# 13_iMX_8X_SYSTEM.net
KiCad netlist of a schematic drawn in Altium Designer
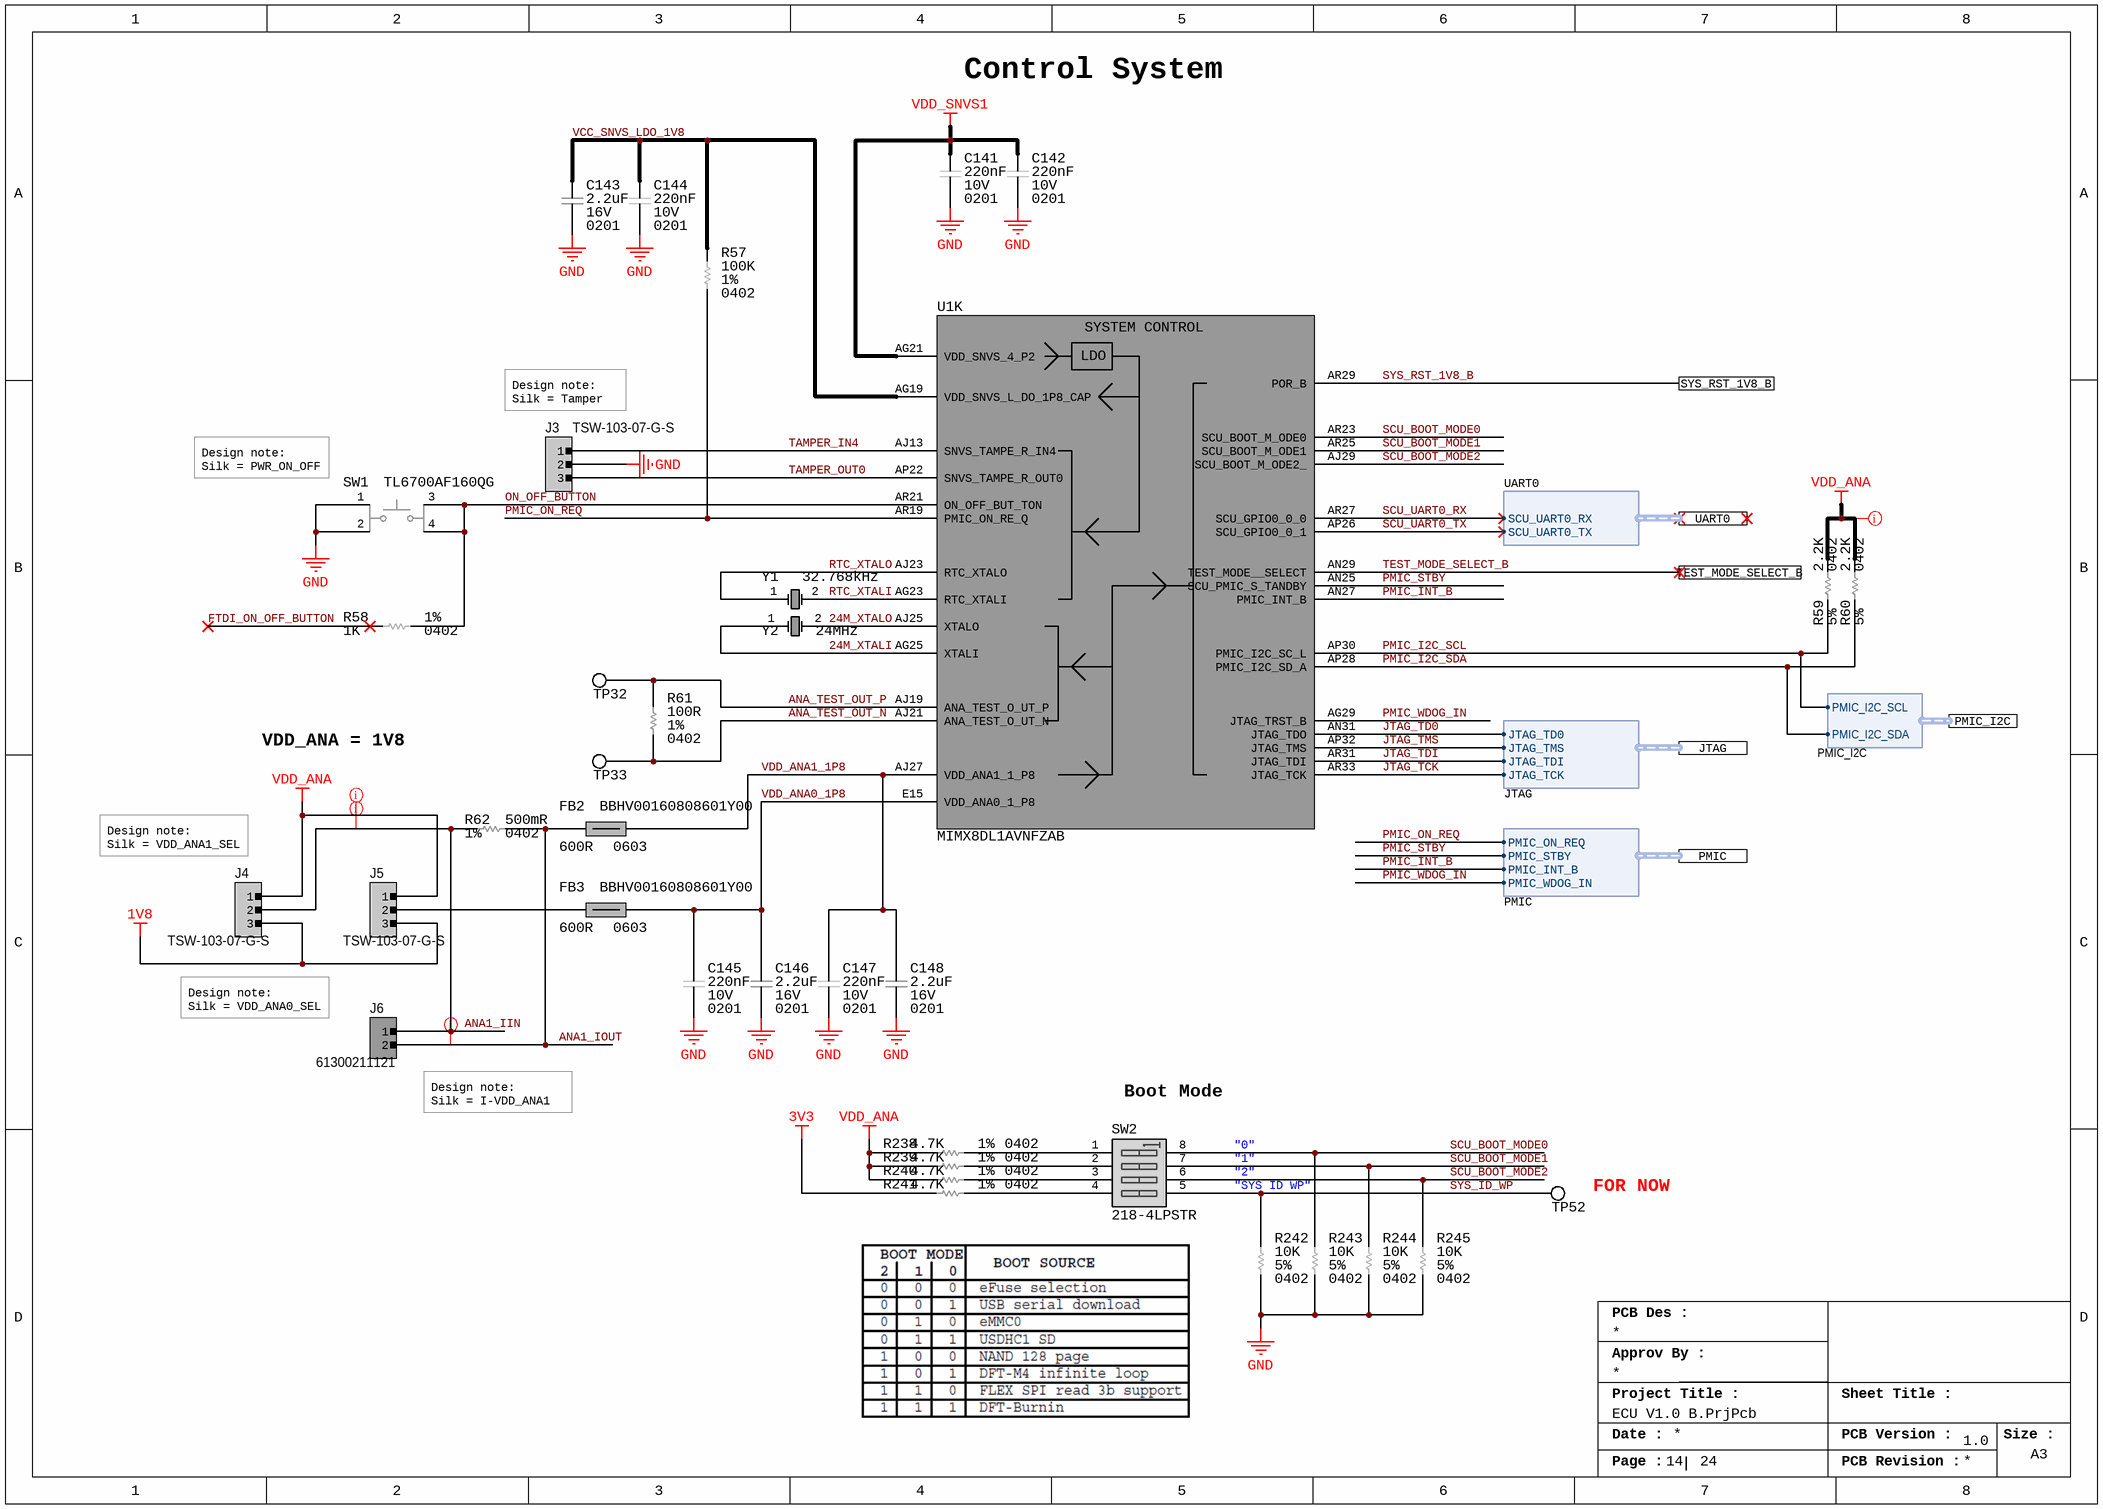
[diagram p0: 13_iMX 8X_SYSTEM.SchDoc]

(export (version "E")
  (design (tool "Eeschema 10.0.6"))
  (components
    (comp (ref "C141")
      (value "LMK063BJ224MP-F")
      (footprint "CAP_0201_CAPC0603X03N")
      (description "Multilayer Ceramic Capacitors (High dielectric type), 10V, 0.22 uF, ± 20 %, 0201, X5R, RoHS")
      (fields
        (field (name "MANUFACTURER") "Taiyo Yuden")
        (field (name "TOLERANCE") "20%")
        (field (name "VOLTAGE RATING (DC)") "10V")
        (field (name "CAPACITANCE") "220nF")
        (field (name "CASE/PACKAGE") "0201")
      )
      (libsource (lib "Electronic Devices_LIB") (part "CAP_0.22UF_10V_X5R_0201"))
    )
    (comp (ref "C142")
      (value "LMK063BJ224MP-F")
      (footprint "CAP_0201_CAPC0603X03N")
      (description "Multilayer Ceramic Capacitors (High dielectric type), 10V, 0.22 uF, ± 20 %, 0201, X5R, RoHS")
      (fields
        (field (name "MANUFACTURER") "Taiyo Yuden")
        (field (name "TOLERANCE") "20%")
        (field (name "VOLTAGE RATING (DC)") "10V")
        (field (name "CAPACITANCE") "220nF")
        (field (name "CASE/PACKAGE") "0201")
      )
      (libsource (lib "Electronic Devices_LIB") (part "CAP_0.22UF_10V_X5R_0201"))
    )
    (comp (ref "C143")
      (value "GRM035R61C225ME01D")
      (footprint "CAP_0201_CAPC0603X03N")
      (description "General Up to 85C Reflow soldering")
      (fields
        (field (name "MANUFACTURER") "Murata")
        (field (name "TOLERANCE") "20%")
        (field (name "CAPACITANCE") "2.2uF")
        (field (name "VOLTAGE RATING") "16V")
        (field (name "CASE/PACKAGE") "0201")
      )
      (libsource (lib "Electronic Devices_LIB") (part "CAP_2.2uF_16V_X5R_0201"))
    )
    (comp (ref "C144")
      (value "LMK063BJ224MP-F")
      (footprint "CAP_0201_CAPC0603X03N")
      (description "Multilayer Ceramic Capacitors (High dielectric type), 10V, 0.22 uF, ± 20 %, 0201, X5R, RoHS")
      (fields
        (field (name "MANUFACTURER") "Taiyo Yuden")
        (field (name "TOLERANCE") "20%")
        (field (name "VOLTAGE RATING (DC)") "10V")
        (field (name "CAPACITANCE") "220nF")
        (field (name "CASE/PACKAGE") "0201")
      )
      (libsource (lib "Electronic Devices_LIB") (part "CAP_0.22UF_10V_X5R_0201"))
    )
    (comp (ref "C145")
      (value "LMK063BJ224MP-F")
      (footprint "CAP_0201_CAPC0603X03N")
      (description "Multilayer Ceramic Capacitors (High dielectric type), 10V, 0.22 uF, ± 20 %, 0201, X5R, RoHS")
      (fields
        (field (name "MANUFACTURER") "Taiyo Yuden")
        (field (name "TOLERANCE") "20%")
        (field (name "VOLTAGE RATING (DC)") "10V")
        (field (name "CAPACITANCE") "220nF")
        (field (name "CASE/PACKAGE") "0201")
      )
      (libsource (lib "Electronic Devices_LIB") (part "CAP_0.22UF_10V_X5R_0201"))
    )
    (comp (ref "C146")
      (value "GRM035R61C225ME01D")
      (footprint "CAP_0201_CAPC0603X03N")
      (description "General Up to 85C Reflow soldering")
      (fields
        (field (name "MANUFACTURER") "Murata")
        (field (name "TOLERANCE") "20%")
        (field (name "CAPACITANCE") "2.2uF")
        (field (name "VOLTAGE RATING") "16V")
        (field (name "CASE/PACKAGE") "0201")
      )
      (libsource (lib "Electronic Devices_LIB") (part "CAP_2.2uF_16V_X5R_0201"))
    )
    (comp (ref "C147")
      (value "LMK063BJ224MP-F")
      (footprint "CAP_0201_CAPC0603X03N")
      (description "Multilayer Ceramic Capacitors (High dielectric type), 10V, 0.22 uF, ± 20 %, 0201, X5R, RoHS")
      (fields
        (field (name "MANUFACTURER") "Taiyo Yuden")
        (field (name "TOLERANCE") "20%")
        (field (name "VOLTAGE RATING (DC)") "10V")
        (field (name "CAPACITANCE") "220nF")
        (field (name "CASE/PACKAGE") "0201")
      )
      (libsource (lib "Electronic Devices_LIB") (part "CAP_0.22UF_10V_X5R_0201"))
    )
    (comp (ref "C148")
      (value "GRM035R61C225ME01D")
      (footprint "CAP_0201_CAPC0603X03N")
      (description "General Up to 85C Reflow soldering")
      (fields
        (field (name "MANUFACTURER") "Murata")
        (field (name "TOLERANCE") "20%")
        (field (name "CAPACITANCE") "2.2uF")
        (field (name "VOLTAGE RATING") "16V")
        (field (name "CASE/PACKAGE") "0201")
      )
      (libsource (lib "Electronic Devices_LIB") (part "CAP_2.2uF_16V_X5R_0201"))
    )
    (comp (ref "FB2")
      (value "BBHV00160808601Y00")
      (footprint "IND_0603_INDC1608X08N")
      (description "Ferrite Chip Bead 600Ohm 2A 0.1Ohm Multilayer 2-Pin 0603 T/R")
      (fields
        (field (name "MANUFACTURER") "Pulse")
        (field (name "IMPEDANCE") "600R")
        (field (name "CASE") "0603")
      )
      (libsource (lib "Electronic Devices_LIB") (part "IND_FERRITE_BEADS_600R_2A_BBHV00160808601Y00"))
    )
    (comp (ref "FB3")
      (value "BBHV00160808601Y00")
      (footprint "IND_0603_INDC1608X08N")
      (description "Ferrite Chip Bead 600Ohm 2A 0.1Ohm Multilayer 2-Pin 0603 T/R")
      (fields
        (field (name "MANUFACTURER") "Pulse")
        (field (name "IMPEDANCE") "600R")
        (field (name "CASE") "0603")
      )
      (libsource (lib "Electronic Devices_LIB") (part "IND_FERRITE_BEADS_600R_2A_BBHV00160808601Y00"))
    )
    (comp (ref "J3")
      (value "TSW-103-07-G-S")
      (footprint "CONN_HEADER_MALE_SAMTEC_TSW-103-07-G-S")
      (description "Conn Unshrouded Header HDR 3 POS 2.54mm Solder ST Top Entry Thru-Hole Bulk")
      (fields (field (name "MANUFACTURER") "Samtec"))
      (libsource (lib "Electronic Devices_LIB") (part "CONN_HEADER_MALE_3P_2.54mm_TSW-103-07-G-S"))
    )
    (comp (ref "J4")
      (value "TSW-103-07-G-S")
      (footprint "CONN_HEADER_MALE_SAMTEC_TSW-103-07-G-S")
      (description "Conn Unshrouded Header HDR 3 POS 2.54mm Solder ST Top Entry Thru-Hole Bulk")
      (fields (field (name "MANUFACTURER") "Samtec"))
      (libsource (lib "Electronic Devices_LIB") (part "CONN_HEADER_MALE_3P_2.54mm_TSW-103-07-G-S"))
    )
    (comp (ref "J5")
      (value "TSW-103-07-G-S")
      (footprint "CONN_HEADER_MALE_SAMTEC_TSW-103-07-G-S")
      (description "Conn Unshrouded Header HDR 3 POS 2.54mm Solder ST Top Entry Thru-Hole Bulk")
      (fields (field (name "MANUFACTURER") "Samtec"))
      (libsource (lib "Electronic Devices_LIB") (part "CONN_HEADER_MALE_3P_2.54mm_TSW-103-07-G-S"))
    )
    (comp (ref "J6")
      (value "61300211121")
      (footprint "HEADER_MALE_HDRV2W110P0X254_1X2_508X254X854P")
      (description "THT Vertical Pin Header WR-PHD, Pitch 2.54 mm, Single Row, 2 pins")
      (fields (field (name "MANUFACTURER") "Wurth Electronics"))
      (libsource (lib "Electronic Devices_LIB") (part "CONN_HEADER_MALE_2P_2.54_61300211121"))
    )
    (comp (ref "R57")
      (value "RC0402FR-07100KL")
      (footprint "RES_0402_RESC1005X04N")
      (description "SMD Chip Resistor, 100 kOhm, ± 1%, 63 mW, 0402 [1005 Metric], Thick Film, General Purpose")
      (fields
        (field (name "MANUFACTURER") "Yageo")
        (field (name "RESISTANCE") "100K")
        (field (name "TOLERANCE") "1%")
        (field (name "CASE/PACKAGE") "0402")
      )
      (libsource (lib "Electronic Devices_LIB") (part "RES_100K_1%_100mW_0402"))
    )
    (comp (ref "R58")
      (value "ERJ-2RKF1001X")
      (footprint "RES_0402_RESC1005X04N")
      (description "RES SMD 1K OHM 1% 1/10W 0402")
      (fields
        (field (name "MANUFACTURER") "Panasonic")
        (field (name "RESISTANCE") "1K")
        (field (name "TOLERANCE") "1%")
        (field (name "CASE/PACKAGE") "0402")
      )
      (libsource (lib "Electronic Devices_LIB") (part "RES_1K_1%_100mW_0402"))
    )
    (comp (ref "R59")
      (value "RC0402JR-072K2L")
      (footprint "RES_0402_RESC1005X04N")
      (description "SMD Chip Resistor, 2.2 kOhm, ± 5%, 63 mW, 0402 [1005 Metric], Thick Film, General Purpose")
      (fields
        (field (name "MANUFACTURER") "Yageo")
        (field (name "TOLERANCE") "5%")
        (field (name "RESISTANCE") "2.2K")
        (field (name "CASE/PACKAGE") "0402")
      )
      (libsource (lib "Electronic Devices_LIB") (part "RES_2.2K_5%_63mW_0402"))
    )
    (comp (ref "R60")
      (value "RC0402JR-072K2L")
      (footprint "RES_0402_RESC1005X04N")
      (description "SMD Chip Resistor, 2.2 kOhm, ± 5%, 63 mW, 0402 [1005 Metric], Thick Film, General Purpose")
      (fields
        (field (name "MANUFACTURER") "Yageo")
        (field (name "TOLERANCE") "5%")
        (field (name "RESISTANCE") "2.2K")
        (field (name "CASE/PACKAGE") "0402")
      )
      (libsource (lib "Electronic Devices_LIB") (part "RES_2.2K_5%_63mW_0402"))
    )
    (comp (ref "R61")
      (value "ERJ-2RKF1000X")
      (footprint "RES_0402_RESC1005X04N")
      (description "Resistor Thick Film 0402 100 Ohm 1% 1/10W 100ppm/C Molded SMD Punched Carrier T/R")
      (fields
        (field (name "MANUFACTURER") "Panasonic")
        (field (name "TOLERANCE") "1%")
        (field (name "RESISTANCE") "100R")
        (field (name "CASE/PACKAGE") "0402")
      )
      (libsource (lib "Electronic Devices_LIB") (part "RES_100R_1%_100mW_0402"))
    )
    (comp (ref "R62")
      (value "RL0402FR-070R5L")
      (footprint "RES_0603_RESC1608X04N")
      (description "SMD Current Sense Resistor, 0.5 ohm, RL Series, 0402 [1005 Metric], 63 mW, ï¿½ 1%, Thick Film")
      (fields
        (field (name "MANUFACTURER") "Yageo")
        (field (name "CASE/PACKAGE") "0402")
        (field (name "TOLERANCE") "1%")
        (field (name "RESISTANCE") "500mR")
      )
      (libsource (lib "Electronic Devices_LIB") (part "RES_0.5R_63mW_0402"))
    )
    (comp (ref "R238")
      (value "ERJ-2RKF4701X")
      (footprint "RES_0402_RESC1005X04N")
      (description "Res Thick Film 0402 4.7K Ohm 1% 0.1W ±100ppm/°C Molded SMD Punched Carrier T/R")
      (fields
        (field (name "MANUFACTURER") "Panasonic")
        (field (name "TOLERANCE") "1%")
        (field (name "CASE CODE (IMPERIAL)") "0402")
        (field (name "RESISTANCE") "4.7K")
      )
      (libsource (lib "Electronic Devices_LIB") (part "RES_4.7K_1%_100mW_0402"))
    )
    (comp (ref "R239")
      (value "ERJ-2RKF4701X")
      (footprint "RES_0402_RESC1005X04N")
      (description "Res Thick Film 0402 4.7K Ohm 1% 0.1W ±100ppm/°C Molded SMD Punched Carrier T/R")
      (fields
        (field (name "MANUFACTURER") "Panasonic")
        (field (name "TOLERANCE") "1%")
        (field (name "CASE CODE (IMPERIAL)") "0402")
        (field (name "RESISTANCE") "4.7K")
      )
      (libsource (lib "Electronic Devices_LIB") (part "RES_4.7K_1%_100mW_0402"))
    )
    (comp (ref "R240")
      (value "ERJ-2RKF4701X")
      (footprint "RES_0402_RESC1005X04N")
      (description "Res Thick Film 0402 4.7K Ohm 1% 0.1W ±100ppm/°C Molded SMD Punched Carrier T/R")
      (fields
        (field (name "MANUFACTURER") "Panasonic")
        (field (name "TOLERANCE") "1%")
        (field (name "CASE CODE (IMPERIAL)") "0402")
        (field (name "RESISTANCE") "4.7K")
      )
      (libsource (lib "Electronic Devices_LIB") (part "RES_4.7K_1%_100mW_0402"))
    )
    (comp (ref "R241")
      (value "ERJ-2RKF4701X")
      (footprint "RES_0402_RESC1005X04N")
      (description "Res Thick Film 0402 4.7K Ohm 1% 0.1W ±100ppm/°C Molded SMD Punched Carrier T/R")
      (fields
        (field (name "MANUFACTURER") "Panasonic")
        (field (name "TOLERANCE") "1%")
        (field (name "CASE CODE (IMPERIAL)") "0402")
        (field (name "RESISTANCE") "4.7K")
      )
      (libsource (lib "Electronic Devices_LIB") (part "RES_4.7K_1%_100mW_0402"))
    )
    (comp (ref "R242")
      (value "ERJ-2GEJ103X")
      (footprint "RES_0402_RESC1005X04N")
      (description "Res Thick Film 0402 10K Ohm 5% 1/10W ±200ppm/°C Molded SMD Punched Carrier T/R")
      (fields
        (field (name "MANUFACTURER") "Panasonic")
        (field (name "TOLERANCE") "5%")
        (field (name "RESISTANCE") "10K")
        (field (name "CASE/PACKAGE") "0402")
      )
      (libsource (lib "Electronic Devices_LIB") (part "RES_10K_5%_100mW_0402"))
    )
    (comp (ref "R243")
      (value "ERJ-2GEJ103X")
      (footprint "RES_0402_RESC1005X04N")
      (description "Res Thick Film 0402 10K Ohm 5% 1/10W ±200ppm/°C Molded SMD Punched Carrier T/R")
      (fields
        (field (name "MANUFACTURER") "Panasonic")
        (field (name "TOLERANCE") "5%")
        (field (name "RESISTANCE") "10K")
        (field (name "CASE/PACKAGE") "0402")
      )
      (libsource (lib "Electronic Devices_LIB") (part "RES_10K_5%_100mW_0402"))
    )
    (comp (ref "R244")
      (value "ERJ-2GEJ103X")
      (footprint "RES_0402_RESC1005X04N")
      (description "Res Thick Film 0402 10K Ohm 5% 1/10W ±200ppm/°C Molded SMD Punched Carrier T/R")
      (fields
        (field (name "MANUFACTURER") "Panasonic")
        (field (name "TOLERANCE") "5%")
        (field (name "RESISTANCE") "10K")
        (field (name "CASE/PACKAGE") "0402")
      )
      (libsource (lib "Electronic Devices_LIB") (part "RES_10K_5%_100mW_0402"))
    )
    (comp (ref "R245")
      (value "ERJ-2GEJ103X")
      (footprint "RES_0402_RESC1005X04N")
      (description "Res Thick Film 0402 10K Ohm 5% 1/10W ±200ppm/°C Molded SMD Punched Carrier T/R")
      (fields
        (field (name "MANUFACTURER") "Panasonic")
        (field (name "TOLERANCE") "5%")
        (field (name "RESISTANCE") "10K")
        (field (name "CASE/PACKAGE") "0402")
      )
      (libsource (lib "Electronic Devices_LIB") (part "RES_10K_5%_100mW_0402"))
    )
    (comp (ref "SW1")
      (value "TL6700AF160QG")
      (footprint "SW_TL6700AF160QG")
      (description "TL6700 Series SPST 1.6 N Round Button Gull Wing SMT Sealed Tactile Switch")
      (fields (field (name "MANUFACTURER") "E-Switch"))
      (libsource (lib "Electronic Devices_LIB") (part "SWITCH_SPST_TL6700AF160QG"))
    )
    (comp (ref "SW2")
      (value "218-4LPSTR")
      (footprint "SW_DIP_SOIC127P844X265-8N")
      (description "Switch DIP ON OFF SPST 4 Recessed Slide 0.025A 24VDC Gull Wing 1000Cycles 1.27mm SMD T/R")
      (fields (field (name "MANUFACTURER") "CTS"))
      (libsource (lib "Electronic Devices_LIB") (part "SWITCH_DIP_4P_25mA_218-4LPSTR"))
    )
    (comp (ref "TP32")
      (value "NO COMPONENT")
      (footprint "TP_PAD_0.5MM_SMD_ROUND")
      (description "Test Point, SMD pad, round, 1.5mm, 1.6mm, 3mm diameter")
      (libsource (lib "Electronic Devices_LIB") (part "TP_PAD_SMD_SMALL"))
    )
    (comp (ref "TP33")
      (value "NO COMPONENT")
      (footprint "TP_PAD_0.5MM_SMD_ROUND")
      (description "Test Point, SMD pad, round, 1.5mm, 1.6mm, 3mm diameter")
      (libsource (lib "Electronic Devices_LIB") (part "TP_PAD_SMD_SMALL"))
    )
    (comp (ref "TP52")
      (value "NO COMPONENT")
      (footprint "TP_PAD_0.5MM_SMD_ROUND")
      (description "Test Point, SMD pad, round, 1.5mm, 1.6mm, 3mm diameter")
      (libsource (lib "Electronic Devices_LIB") (part "TP_PAD_SMD_SMALL"))
    )
    (comp (ref "U1")
      (value "MIMX8DL1AVNFZAB")
      (footprint "MIMX8DL1AVNFZAB")
      (description "I.MX8 Dxl 15SQ / Tray Rohs Compliant: Yes")
      (fields (field (name "MANUFACTURER") "NXP Semiconductors"))
      (libsource (lib "Electronic Devices_LIB") (part "IC_MPU_ARM_1.2GHz_MIMX8DL1AVNFZAB"))
    )
    (comp (ref "Y1")
      (value "FC-135 32.7680KA-AG5")
      (footprint "CRYSTAL_FC135327680KAAG5")
      (description "Crystal 0.032768MHz ±20ppm (Tol) 7pF FUND 70000Ohm 2-Pin SMD T/R")
      (fields (field (name "MANUFACTURER") "Epson") (field (name "FREQUENCY") "32.768kHz"))
      (libsource (lib "Electronic Devices_LIB") (part "CRYSTAL_EPSON_32.768KHZ"))
    )
    (comp (ref "Y2")
      (value "ECS-240-18-23A-EN-TR")
      (footprint "CRYSTAL_ECS-240-18-23A-EN-TR")
      (description "Crystal 24MHz ±30ppm (Tol) ±50ppm (Stability) 18pF FUND 30Ohm 2-Pin Mini-SMD T/R")
      (fields (field (name "MANUFACTURER") "ECS International") (field (name "FREQUENCY") "24MHz"))
      (libsource (lib "Electronic Devices_LIB") (part "CRYSTAL_ECS_24MHZ"))
    )
  )
  (nets
    (net (code "5") (name "/24M_XTALI") (class "Default")
      (node (ref "U1") (pin "AG25") (pinfunction "XTALI_AG25") (pintype "passive"))
      (node (ref "Y2") (pin "1") (pinfunction "OSC1_1") (pintype "passive"))
    )
    (net (code "6") (name "/24M_XTALO") (class "Default")
      (node (ref "U1") (pin "AJ25") (pinfunction "XTALO_AJ25") (pintype "passive"))
      (node (ref "Y2") (pin "2") (pinfunction "OSC2_2") (pintype "passive"))
    )
    (net (code "7") (name "/ANA1_IIN") (class "Default")
      (node (ref "J4") (pin "2") (pinfunction "2_2") (pintype "passive"))
      (node (ref "J6") (pin "1") (pinfunction "1_1") (pintype "passive"))
      (node (ref "R62") (pin "1") (pinfunction "1_1") (pintype "passive"))
    )
    (net (code "8") (name "/ANA1_IOUT") (class "Default")
      (node (ref "FB2") (pin "1") (pinfunction "1_1") (pintype "passive"))
      (node (ref "J6") (pin "2") (pinfunction "2_2") (pintype "passive"))
      (node (ref "R62") (pin "2") (pinfunction "2_2") (pintype "passive"))
    )
    (net (code "9") (name "/ANA_TEST_OUT_N") (class "Default")
      (node (ref "R61") (pin "1") (pinfunction "1_1") (pintype "passive"))
      (node (ref "TP33") (pin "1") (pinfunction "1_1") (pintype "passive"))
      (node (ref "U1") (pin "AJ21") (pinfunction "ANA_TEST_O_UT_N_AJ21") (pintype "passive"))
    )
    (net (code "10") (name "/ANA_TEST_OUT_P") (class "Default")
      (node (ref "R61") (pin "2") (pinfunction "2_2") (pintype "passive"))
      (node (ref "TP32") (pin "1") (pinfunction "1_1") (pintype "passive"))
      (node (ref "U1") (pin "AJ19") (pinfunction "ANA_TEST_O_UT_P_AJ19") (pintype "passive"))
    )
    (net (code "11") (name "/FTDI_ON_OFF_BUTTON") (class "Default")
      (node (ref "R58") (pin "1") (pinfunction "1_1") (pintype "passive+no_connect"))
    )
    (net (code "12") (name "/JTAG_TCK") (class "Default")
      (node (ref "U1") (pin "AR33") (pinfunction "JTAG_TCK_AR33") (pintype "passive"))
    )
    (net (code "13") (name "/JTAG_TD0") (class "Default")
      (node (ref "U1") (pin "AN31") (pinfunction "JTAG_TDO_AN31") (pintype "passive"))
    )
    (net (code "14") (name "/JTAG_TDI") (class "Default")
      (node (ref "U1") (pin "AR31") (pinfunction "JTAG_TDI_AR31") (pintype "passive"))
    )
    (net (code "15") (name "/JTAG_TMS") (class "Default")
      (node (ref "U1") (pin "AP32") (pinfunction "JTAG_TMS_AP32") (pintype "passive"))
    )
    (net (code "16") (name "/ON_OFF_BUTTON") (class "Default")
      (node (ref "R58") (pin "2") (pinfunction "2_2") (pintype "passive"))
      (node (ref "SW1") (pin "3") (pinfunction "3_3") (pintype "passive"))
      (node (ref "SW1") (pin "4") (pinfunction "4_4") (pintype "passive"))
      (node (ref "U1") (pin "AR21") (pinfunction "ON_OFF_BUT_TON_AR21") (pintype "passive"))
    )
    (net (code "17") (name "/PMIC_I2C_SCL") (class "Default")
      (node (ref "R59") (pin "1") (pinfunction "1_1") (pintype "passive"))
      (node (ref "U1") (pin "AP30") (pinfunction "PMIC_I2C_SC_L_AP30") (pintype "passive"))
    )
    (net (code "18") (name "/PMIC_I2C_SDA") (class "Default")
      (node (ref "R60") (pin "1") (pinfunction "1_1") (pintype "passive"))
      (node (ref "U1") (pin "AP28") (pinfunction "PMIC_I2C_SD_A_AP28") (pintype "passive"))
    )
    (net (code "19") (name "/PMIC_INT_B") (class "Default")
      (node (ref "U1") (pin "AN27") (pinfunction "PMIC_INT_B_AN27") (pintype "passive"))
    )
    (net (code "20") (name "/PMIC_ON_REQ") (class "Default")
      (node (ref "R57") (pin "1") (pinfunction "1_1") (pintype "passive"))
      (node (ref "U1") (pin "AR19") (pinfunction "PMIC_ON_RE_Q_AR19") (pintype "passive"))
    )
    (net (code "21") (name "/PMIC_STBY") (class "Default")
      (node (ref "U1") (pin "AN25") (pinfunction "SCU_PMIC_S_TANDBY_AN25") (pintype "passive"))
    )
    (net (code "22") (name "/PMIC_WDOG_IN") (class "Default")
      (node (ref "U1") (pin "AG29") (pinfunction "JTAG_TRST_B_AG29") (pintype "passive"))
    )
    (net (code "23") (name "/RTC_XTALI") (class "Default")
      (node (ref "U1") (pin "AG23") (pinfunction "RTC_XTALI_AG23") (pintype "passive"))
      (node (ref "Y1") (pin "2") (pinfunction "OSC2_2") (pintype "passive"))
    )
    (net (code "24") (name "/RTC_XTALO") (class "Default")
      (node (ref "U1") (pin "AJ23") (pinfunction "RTC_XTALO_AJ23") (pintype "passive"))
      (node (ref "Y1") (pin "1") (pinfunction "OSC1_1") (pintype "passive"))
    )
    (net (code "25") (name "/SCU_BOOT_MODE0") (class "Default")
      (node (ref "R243") (pin "1") (pinfunction "1_1") (pintype "passive"))
      (node (ref "SW2") (pin "8") (pinfunction "B1_8") (pintype "passive"))
      (node (ref "U1") (pin "AR23") (pinfunction "SCU_BOOT_M_ODE0_AR23") (pintype "passive"))
    )
    (net (code "26") (name "/SCU_BOOT_MODE1") (class "Default")
      (node (ref "R244") (pin "1") (pinfunction "1_1") (pintype "passive"))
      (node (ref "SW2") (pin "7") (pinfunction "B2_7") (pintype "passive"))
      (node (ref "U1") (pin "AR25") (pinfunction "SCU_BOOT_M_ODE1_AR25") (pintype "passive"))
    )
    (net (code "27") (name "/SCU_BOOT_MODE2") (class "Default")
      (node (ref "R245") (pin "1") (pinfunction "1_1") (pintype "passive"))
      (node (ref "SW2") (pin "6") (pinfunction "B3_6") (pintype "passive"))
      (node (ref "U1") (pin "AJ29") (pinfunction "SCU_BOOT_M_ODE2__AJ29") (pintype "passive"))
    )
    (net (code "28") (name "/SCU_UART0_RX") (class "Default")
      (node (ref "U1") (pin "AR27") (pinfunction "SCU_GPIO0_0_0_AR27") (pintype "passive+no_connect"))
    )
    (net (code "29") (name "/SCU_UART0_TX") (class "Default")
      (node (ref "U1") (pin "AP26") (pinfunction "SCU_GPIO0_0_1_AP26") (pintype "passive+no_connect"))
    )
    (net (code "30") (name "/SYS_ID_WP") (class "Default")
      (node (ref "R242") (pin "1") (pinfunction "1_1") (pintype "passive"))
      (node (ref "SW2") (pin "5") (pinfunction "B4_5") (pintype "passive"))
      (node (ref "TP52") (pin "1") (pinfunction "1_1") (pintype "passive"))
    )
    (net (code "31") (name "/SYS_RST_1V8_B") (class "Default")
      (node (ref "U1") (pin "AR29") (pinfunction "POR_B_AR29") (pintype "passive"))
    )
    (net (code "32") (name "/TAMPER_IN4") (class "Default")
      (node (ref "J3") (pin "1") (pinfunction "1_1") (pintype "passive"))
      (node (ref "U1") (pin "AJ13") (pinfunction "SNVS_TAMPE_R_IN4_AJ13") (pintype "passive"))
    )
    (net (code "33") (name "/TAMPER_OUT0") (class "Default")
      (node (ref "J3") (pin "3") (pinfunction "3_3") (pintype "passive"))
      (node (ref "U1") (pin "AP22") (pinfunction "SNVS_TAMPE_R_OUT0_AP22") (pintype "passive"))
    )
    (net (code "34") (name "/TEST_MODE_SELECT_B") (class "Default")
      (node (ref "U1") (pin "AN29") (pinfunction "TEST_MODE__SELECT_AN29") (pintype "passive+no_connect"))
    )
    (net (code "35") (name "/VCC_SNVS_LDO_1V8") (class "Default")
      (node (ref "C143") (pin "2") (pinfunction "2_2") (pintype "passive"))
      (node (ref "C144") (pin "2") (pinfunction "2_2") (pintype "passive"))
      (node (ref "R57") (pin "2") (pinfunction "2_2") (pintype "passive"))
      (node (ref "U1") (pin "AG19") (pinfunction "VDD_SNVS_L_DO_1P8_CAP_AG19") (pintype "passive"))
    )
    (net (code "36") (name "/VDD_ANA0_1P8") (class "Default")
      (node (ref "C145") (pin "2") (pinfunction "2_2") (pintype "passive"))
      (node (ref "C146") (pin "2") (pinfunction "2_2") (pintype "passive"))
      (node (ref "FB3") (pin "2") (pinfunction "2_2") (pintype "passive"))
      (node (ref "U1") (pin "E15") (pinfunction "VDD_ANA0_1_P8_E15") (pintype "passive"))
    )
    (net (code "37") (name "/VDD_ANA1_1P8") (class "Default")
      (node (ref "C147") (pin "2") (pinfunction "2_2") (pintype "passive"))
      (node (ref "C148") (pin "2") (pinfunction "2_2") (pintype "passive"))
      (node (ref "FB2") (pin "2") (pinfunction "2_2") (pintype "passive"))
      (node (ref "U1") (pin "AJ27") (pinfunction "VDD_ANA1_1_P8_AJ27") (pintype "passive"))
    )
    (net (code "42") (name "1V8") (class "Default")
      (node (ref "J4") (pin "3") (pinfunction "3_3") (pintype "passive"))
      (node (ref "J5") (pin "3") (pinfunction "3_3") (pintype "passive"))
    )
    (net (code "43") (name "3V3") (class "Default")
      (node (ref "R241") (pin "1") (pinfunction "1_1") (pintype "passive"))
    )
    (net (code "44") (name "GND") (class "Default")
      (node (ref "C141") (pin "1") (pinfunction "1_1") (pintype "passive"))
      (node (ref "C142") (pin "1") (pinfunction "1_1") (pintype "passive"))
      (node (ref "C143") (pin "1") (pinfunction "1_1") (pintype "passive"))
      (node (ref "C144") (pin "1") (pinfunction "1_1") (pintype "passive"))
      (node (ref "C145") (pin "1") (pinfunction "1_1") (pintype "passive"))
      (node (ref "C146") (pin "1") (pinfunction "1_1") (pintype "passive"))
      (node (ref "C147") (pin "1") (pinfunction "1_1") (pintype "passive"))
      (node (ref "C148") (pin "1") (pinfunction "1_1") (pintype "passive"))
      (node (ref "J3") (pin "2") (pinfunction "2_2") (pintype "passive"))
      (node (ref "R242") (pin "2") (pinfunction "2_2") (pintype "passive"))
      (node (ref "R243") (pin "2") (pinfunction "2_2") (pintype "passive"))
      (node (ref "R244") (pin "2") (pinfunction "2_2") (pintype "passive"))
      (node (ref "R245") (pin "2") (pinfunction "2_2") (pintype "passive"))
      (node (ref "SW1") (pin "1") (pinfunction "1_1") (pintype "passive"))
      (node (ref "SW1") (pin "2") (pinfunction "2_2") (pintype "passive"))
    )
    (net (code "45") (name "Net-(FB3-Pad1)") (class "Default")
      (node (ref "FB3") (pin "1") (pinfunction "1_1") (pintype "passive"))
      (node (ref "J5") (pin "2") (pinfunction "2_2") (pintype "passive"))
    )
    (net (code "46") (name "Net-(SW2-A1)") (class "Default")
      (node (ref "R238") (pin "2") (pinfunction "2_2") (pintype "passive"))
      (node (ref "SW2") (pin "1") (pinfunction "A1_1") (pintype "passive"))
    )
    (net (code "47") (name "Net-(SW2-A2)") (class "Default")
      (node (ref "R239") (pin "2") (pinfunction "2_2") (pintype "passive"))
      (node (ref "SW2") (pin "2") (pinfunction "A2_2") (pintype "passive"))
    )
    (net (code "48") (name "Net-(SW2-A3)") (class "Default")
      (node (ref "R240") (pin "2") (pinfunction "2_2") (pintype "passive"))
      (node (ref "SW2") (pin "3") (pinfunction "A3_3") (pintype "passive"))
    )
    (net (code "49") (name "Net-(SW2-A4)") (class "Default")
      (node (ref "R241") (pin "2") (pinfunction "2_2") (pintype "passive"))
      (node (ref "SW2") (pin "4") (pinfunction "A4_4") (pintype "passive"))
    )
    (net (code "50") (name "VDD_ANA") (class "Default")
      (node (ref "J4") (pin "1") (pinfunction "1_1") (pintype "passive"))
      (node (ref "J5") (pin "1") (pinfunction "1_1") (pintype "passive"))
      (node (ref "R238") (pin "1") (pinfunction "1_1") (pintype "passive"))
      (node (ref "R239") (pin "1") (pinfunction "1_1") (pintype "passive"))
      (node (ref "R240") (pin "1") (pinfunction "1_1") (pintype "passive"))
      (node (ref "R59") (pin "2") (pinfunction "2_2") (pintype "passive"))
      (node (ref "R60") (pin "2") (pinfunction "2_2") (pintype "passive"))
    )
    (net (code "51") (name "VDD_SNVS1") (class "Default")
      (node (ref "C141") (pin "2") (pinfunction "2_2") (pintype "passive"))
      (node (ref "C142") (pin "2") (pinfunction "2_2") (pintype "passive"))
      (node (ref "U1") (pin "AG21") (pinfunction "VDD_SNVS_4_P2_AG21") (pintype "passive"))
    )
  )
)
